# Test_Motorboard.net
KiCad netlist of a schematic drawn in EAGLE
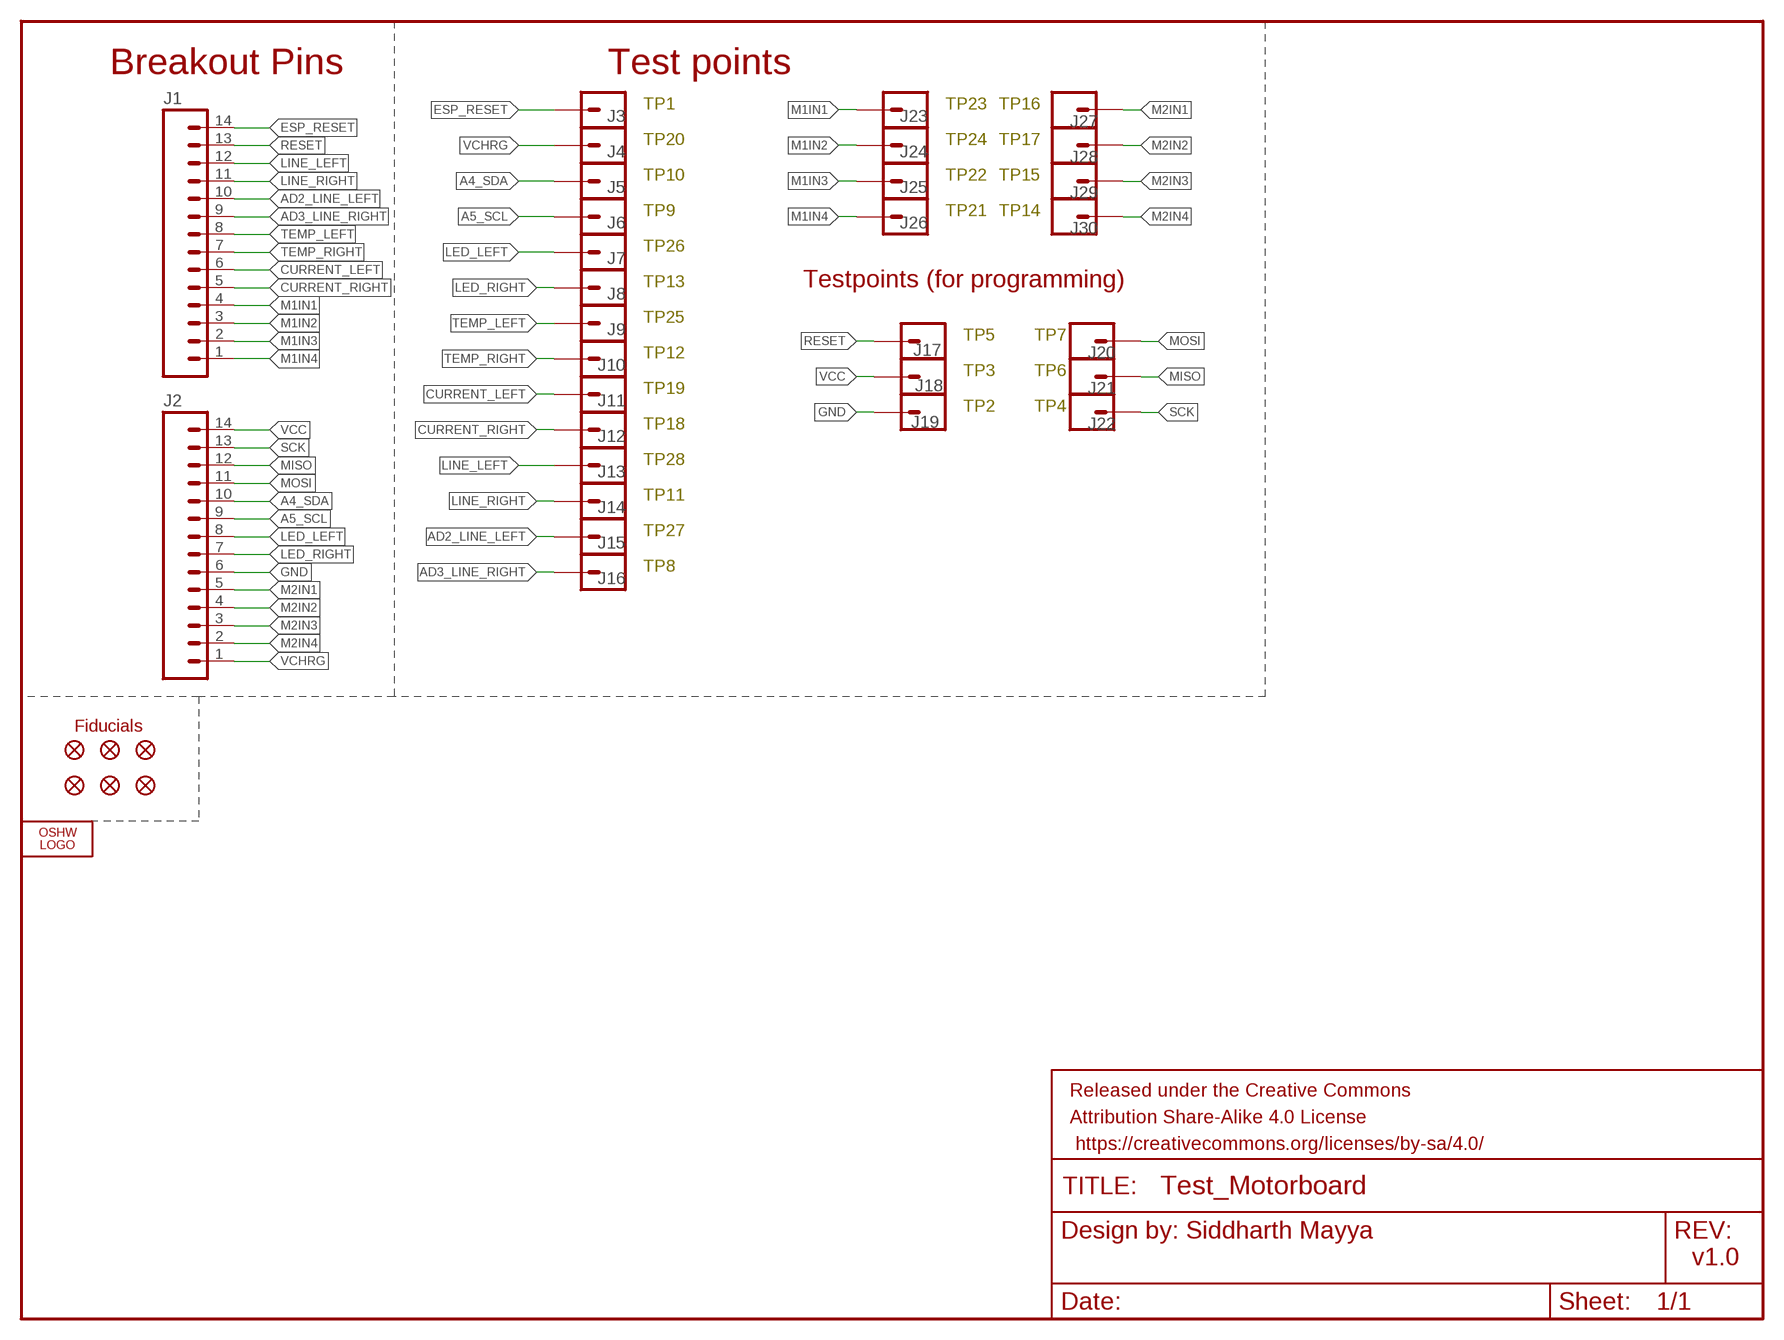
[diagram p0: schematic, sheet 1]

(export (version "E")
  (design (tool "Eeschema 10.0.6"))
  (components
    (comp (ref "FD1")
      (value "FIDUCIAL1X2")
      (footprint "eagle-import:FIDUCIAL-1X2")
      (libsource (lib "eagle-import") (part "FIDUCIAL1X2"))
    )
    (comp (ref "FD2")
      (value "FIDUCIAL1X2")
      (footprint "eagle-import:FIDUCIAL-1X2")
      (libsource (lib "eagle-import") (part "FIDUCIAL1X2"))
    )
    (comp (ref "FD3")
      (value "FIDUCIAL1X2")
      (footprint "eagle-import:FIDUCIAL-1X2")
      (libsource (lib "eagle-import") (part "FIDUCIAL1X2"))
    )
    (comp (ref "FD4")
      (value "FIDUCIAL1X2")
      (footprint "eagle-import:FIDUCIAL-1X2")
      (libsource (lib "eagle-import") (part "FIDUCIAL1X2"))
    )
    (comp (ref "FD5")
      (value "FIDUCIAL1X2")
      (footprint "eagle-import:FIDUCIAL-1X2")
      (libsource (lib "eagle-import") (part "FIDUCIAL1X2"))
    )
    (comp (ref "FD6")
      (value "FIDUCIAL1X2")
      (footprint "eagle-import:FIDUCIAL-1X2")
      (libsource (lib "eagle-import") (part "FIDUCIAL1X2"))
    )
    (comp (ref "FRAME1")
      (value "FRAME-LETTER")
      (footprint "eagle-import:CREATIVE_COMMONS")
      (libsource (lib "eagle-import") (part "FRAME-LETTER"))
    )
    (comp (ref "J1")
      (value "M14")
      (footprint "eagle-import:1X14")
      (libsource (lib "eagle-import") (part "M14"))
    )
    (comp (ref "J2")
      (value "M14")
      (footprint "eagle-import:1X14")
      (libsource (lib "eagle-import") (part "M14"))
    )
    (comp (ref "J3")
      (value "M01PTH")
      (footprint "eagle-import:1X01")
      (libsource (lib "eagle-import") (part "M01PTH"))
    )
    (comp (ref "J4")
      (value "M01PTH")
      (footprint "eagle-import:1X01")
      (libsource (lib "eagle-import") (part "M01PTH"))
    )
    (comp (ref "J5")
      (value "M01PTH")
      (footprint "eagle-import:1X01")
      (libsource (lib "eagle-import") (part "M01PTH"))
    )
    (comp (ref "J6")
      (value "M01PTH")
      (footprint "eagle-import:1X01")
      (libsource (lib "eagle-import") (part "M01PTH"))
    )
    (comp (ref "J7")
      (value "M01PTH")
      (footprint "eagle-import:1X01")
      (libsource (lib "eagle-import") (part "M01PTH"))
    )
    (comp (ref "J8")
      (value "M01PTH")
      (footprint "eagle-import:1X01")
      (libsource (lib "eagle-import") (part "M01PTH"))
    )
    (comp (ref "J9")
      (value "M01PTH")
      (footprint "eagle-import:1X01")
      (libsource (lib "eagle-import") (part "M01PTH"))
    )
    (comp (ref "J10")
      (value "M01PTH")
      (footprint "eagle-import:1X01")
      (libsource (lib "eagle-import") (part "M01PTH"))
    )
    (comp (ref "J11")
      (value "M01PTH")
      (footprint "eagle-import:1X01")
      (libsource (lib "eagle-import") (part "M01PTH"))
    )
    (comp (ref "J12")
      (value "M01PTH")
      (footprint "eagle-import:1X01")
      (libsource (lib "eagle-import") (part "M01PTH"))
    )
    (comp (ref "J13")
      (value "M01PTH")
      (footprint "eagle-import:1X01")
      (libsource (lib "eagle-import") (part "M01PTH"))
    )
    (comp (ref "J14")
      (value "M01PTH")
      (footprint "eagle-import:1X01")
      (libsource (lib "eagle-import") (part "M01PTH"))
    )
    (comp (ref "J15")
      (value "M01PTH")
      (footprint "eagle-import:1X01")
      (libsource (lib "eagle-import") (part "M01PTH"))
    )
    (comp (ref "J16")
      (value "M01PTH")
      (footprint "eagle-import:1X01")
      (libsource (lib "eagle-import") (part "M01PTH"))
    )
    (comp (ref "J17")
      (value "M01PTH")
      (footprint "eagle-import:1X01")
      (libsource (lib "eagle-import") (part "M01PTH"))
    )
    (comp (ref "J18")
      (value "M01PTH")
      (footprint "eagle-import:1X01")
      (libsource (lib "eagle-import") (part "M01PTH"))
    )
    (comp (ref "J19")
      (value "M01PTH")
      (footprint "eagle-import:1X01")
      (libsource (lib "eagle-import") (part "M01PTH"))
    )
    (comp (ref "J20")
      (value "M01PTH")
      (footprint "eagle-import:1X01")
      (libsource (lib "eagle-import") (part "M01PTH"))
    )
    (comp (ref "J21")
      (value "M01PTH")
      (footprint "eagle-import:1X01")
      (libsource (lib "eagle-import") (part "M01PTH"))
    )
    (comp (ref "J22")
      (value "M01PTH")
      (footprint "eagle-import:1X01")
      (libsource (lib "eagle-import") (part "M01PTH"))
    )
    (comp (ref "J23")
      (value "M01PTH")
      (footprint "eagle-import:1X01")
      (libsource (lib "eagle-import") (part "M01PTH"))
    )
    (comp (ref "J24")
      (value "M01PTH")
      (footprint "eagle-import:1X01")
      (libsource (lib "eagle-import") (part "M01PTH"))
    )
    (comp (ref "J25")
      (value "M01PTH")
      (footprint "eagle-import:1X01")
      (libsource (lib "eagle-import") (part "M01PTH"))
    )
    (comp (ref "J26")
      (value "M01PTH")
      (footprint "eagle-import:1X01")
      (libsource (lib "eagle-import") (part "M01PTH"))
    )
    (comp (ref "J27")
      (value "M01PTH")
      (footprint "eagle-import:1X01")
      (libsource (lib "eagle-import") (part "M01PTH"))
    )
    (comp (ref "J28")
      (value "M01PTH")
      (footprint "eagle-import:1X01")
      (libsource (lib "eagle-import") (part "M01PTH"))
    )
    (comp (ref "J29")
      (value "M01PTH")
      (footprint "eagle-import:1X01")
      (libsource (lib "eagle-import") (part "M01PTH"))
    )
    (comp (ref "J30")
      (value "M01PTH")
      (footprint "eagle-import:1X01")
      (libsource (lib "eagle-import") (part "M01PTH"))
    )
    (comp (ref "LOGO1")
      (value "OSHW_LOGO_FILLX0100-NT")
      (footprint "eagle-import:OSHW_FILLX100_NOTEXT")
      (libsource (lib "eagle-import") (part "OSHW_LOGO_FILLX0100-NT"))
    )
  )
  (nets
    (net (code "1") (name "A4_SDA") (class "Default")
      (node (ref "J2") (pin "10") (pinfunction "10_10") (pintype "passive"))
      (node (ref "J5") (pin "1") (pinfunction "1_1") (pintype "passive"))
    )
    (net (code "2") (name "A5_SCL") (class "Default")
      (node (ref "J2") (pin "9") (pinfunction "9_9") (pintype "passive"))
      (node (ref "J6") (pin "1") (pinfunction "1_1") (pintype "passive"))
    )
    (net (code "3") (name "AD2_LINE_LEFT") (class "Default")
      (node (ref "J1") (pin "10") (pinfunction "10_10") (pintype "passive"))
      (node (ref "J15") (pin "1") (pinfunction "1_1") (pintype "passive"))
    )
    (net (code "4") (name "AD3_LINE_RIGHT") (class "Default")
      (node (ref "J1") (pin "9") (pinfunction "9_9") (pintype "passive"))
      (node (ref "J16") (pin "1") (pinfunction "1_1") (pintype "passive"))
    )
    (net (code "5") (name "CURRENT_LEFT") (class "Default")
      (node (ref "J1") (pin "6") (pinfunction "6_6") (pintype "passive"))
      (node (ref "J11") (pin "1") (pinfunction "1_1") (pintype "passive"))
    )
    (net (code "6") (name "CURRENT_RIGHT") (class "Default")
      (node (ref "J1") (pin "5") (pinfunction "5_5") (pintype "passive"))
      (node (ref "J12") (pin "1") (pinfunction "1_1") (pintype "passive"))
    )
    (net (code "7") (name "ESP_RESET") (class "Default")
      (node (ref "J1") (pin "14") (pinfunction "14_14") (pintype "passive"))
      (node (ref "J3") (pin "1") (pinfunction "1_1") (pintype "passive"))
    )
    (net (code "8") (name "GND") (class "Default")
      (node (ref "J19") (pin "1") (pinfunction "1_1") (pintype "passive"))
      (node (ref "J2") (pin "6") (pinfunction "6_6") (pintype "passive"))
    )
    (net (code "9") (name "LED_LEFT") (class "Default")
      (node (ref "J2") (pin "8") (pinfunction "8_8") (pintype "passive"))
      (node (ref "J7") (pin "1") (pinfunction "1_1") (pintype "passive"))
    )
    (net (code "10") (name "LED_RIGHT") (class "Default")
      (node (ref "J2") (pin "7") (pinfunction "7_7") (pintype "passive"))
      (node (ref "J8") (pin "1") (pinfunction "1_1") (pintype "passive"))
    )
    (net (code "11") (name "LINE_LEFT") (class "Default")
      (node (ref "J1") (pin "12") (pinfunction "12_12") (pintype "passive"))
      (node (ref "J13") (pin "1") (pinfunction "1_1") (pintype "passive"))
    )
    (net (code "12") (name "LINE_RIGHT") (class "Default")
      (node (ref "J1") (pin "11") (pinfunction "11_11") (pintype "passive"))
      (node (ref "J14") (pin "1") (pinfunction "1_1") (pintype "passive"))
    )
    (net (code "13") (name "M1IN1") (class "Default")
      (node (ref "J1") (pin "4") (pinfunction "4_4") (pintype "passive"))
      (node (ref "J23") (pin "1") (pinfunction "1_1") (pintype "passive"))
    )
    (net (code "14") (name "M1IN2") (class "Default")
      (node (ref "J1") (pin "3") (pinfunction "3_3") (pintype "passive"))
      (node (ref "J24") (pin "1") (pinfunction "1_1") (pintype "passive"))
    )
    (net (code "15") (name "M1IN3") (class "Default")
      (node (ref "J1") (pin "2") (pinfunction "2_2") (pintype "passive"))
      (node (ref "J25") (pin "1") (pinfunction "1_1") (pintype "passive"))
    )
    (net (code "16") (name "M1IN4") (class "Default")
      (node (ref "J1") (pin "1") (pinfunction "1_1") (pintype "passive"))
      (node (ref "J26") (pin "1") (pinfunction "1_1") (pintype "passive"))
    )
    (net (code "17") (name "M2IN1") (class "Default")
      (node (ref "J2") (pin "5") (pinfunction "5_5") (pintype "passive"))
      (node (ref "J27") (pin "1") (pinfunction "1_1") (pintype "passive"))
    )
    (net (code "18") (name "M2IN2") (class "Default")
      (node (ref "J2") (pin "4") (pinfunction "4_4") (pintype "passive"))
      (node (ref "J28") (pin "1") (pinfunction "1_1") (pintype "passive"))
    )
    (net (code "19") (name "M2IN3") (class "Default")
      (node (ref "J2") (pin "3") (pinfunction "3_3") (pintype "passive"))
      (node (ref "J29") (pin "1") (pinfunction "1_1") (pintype "passive"))
    )
    (net (code "20") (name "M2IN4") (class "Default")
      (node (ref "J2") (pin "2") (pinfunction "2_2") (pintype "passive"))
      (node (ref "J30") (pin "1") (pinfunction "1_1") (pintype "passive"))
    )
    (net (code "21") (name "MISO") (class "Default")
      (node (ref "J2") (pin "12") (pinfunction "12_12") (pintype "passive"))
      (node (ref "J21") (pin "1") (pinfunction "1_1") (pintype "passive"))
    )
    (net (code "22") (name "MOSI") (class "Default")
      (node (ref "J2") (pin "11") (pinfunction "11_11") (pintype "passive"))
      (node (ref "J20") (pin "1") (pinfunction "1_1") (pintype "passive"))
    )
    (net (code "23") (name "RESET") (class "Default")
      (node (ref "J1") (pin "13") (pinfunction "13_13") (pintype "passive"))
      (node (ref "J17") (pin "1") (pinfunction "1_1") (pintype "passive"))
    )
    (net (code "24") (name "SCK") (class "Default")
      (node (ref "J2") (pin "13") (pinfunction "13_13") (pintype "passive"))
      (node (ref "J22") (pin "1") (pinfunction "1_1") (pintype "passive"))
    )
    (net (code "25") (name "TEMP_LEFT") (class "Default")
      (node (ref "J1") (pin "8") (pinfunction "8_8") (pintype "passive"))
      (node (ref "J9") (pin "1") (pinfunction "1_1") (pintype "passive"))
    )
    (net (code "26") (name "TEMP_RIGHT") (class "Default")
      (node (ref "J1") (pin "7") (pinfunction "7_7") (pintype "passive"))
      (node (ref "J10") (pin "1") (pinfunction "1_1") (pintype "passive"))
    )
    (net (code "27") (name "VCC") (class "Default")
      (node (ref "J18") (pin "1") (pinfunction "1_1") (pintype "passive"))
      (node (ref "J2") (pin "14") (pinfunction "14_14") (pintype "passive"))
    )
    (net (code "28") (name "VCHRG") (class "Default")
      (node (ref "J2") (pin "1") (pinfunction "1_1") (pintype "passive"))
      (node (ref "J4") (pin "1") (pinfunction "1_1") (pintype "passive"))
    )
  )
)
